# LSF0204-Breakout.net
KiCad netlist of a schematic drawn in EAGLE
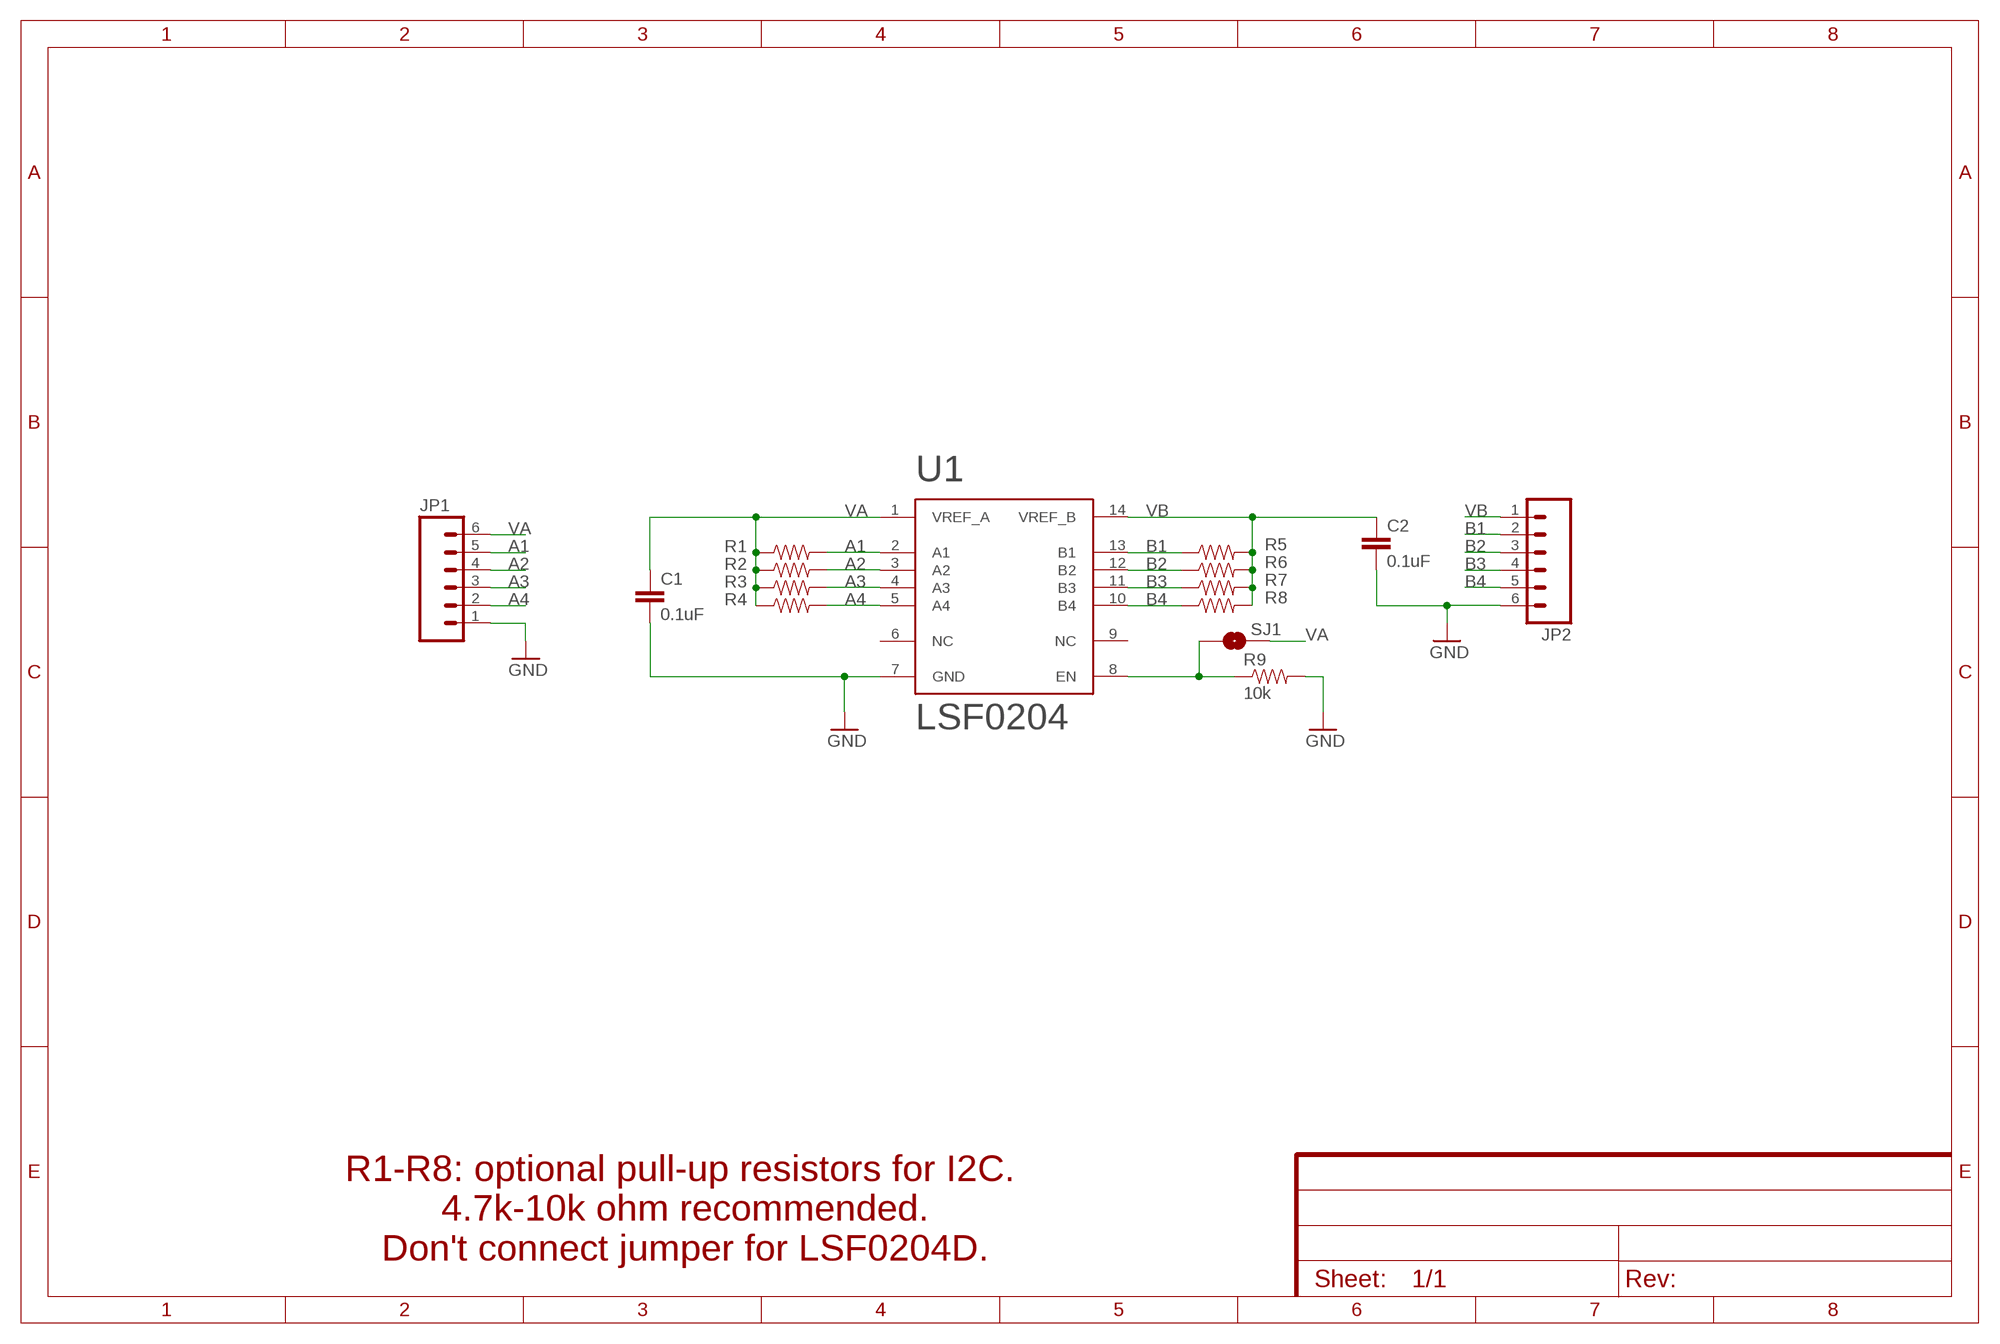
[diagram p0: schematic, sheet 1]

(export (version "E")
  (design (tool "Eeschema 10.0.6"))
  (components
    (comp (ref "C1")
      (value "0.1uF")
      (footprint "eagle-import:0805")
      (libsource (lib "eagle-import") (part "CAP0805"))
    )
    (comp (ref "C2")
      (value "0.1uF")
      (footprint "eagle-import:0805")
      (libsource (lib "eagle-import") (part "CAP0805"))
    )
    (comp (ref "JP1")
      (value "M06LOCK")
      (footprint "eagle-import:1X06_LOCK")
      (libsource (lib "eagle-import") (part "M06LOCK"))
    )
    (comp (ref "JP2")
      (value "M06LOCK")
      (footprint "eagle-import:1X06_LOCK")
      (libsource (lib "eagle-import") (part "M06LOCK"))
    )
    (comp (ref "R1")
      (value "RESISTOR0805-RES")
      (footprint "eagle-import:0805")
      (libsource (lib "eagle-import") (part "RESISTOR0805-RES"))
    )
    (comp (ref "R2")
      (value "RESISTOR0805-RES")
      (footprint "eagle-import:0805")
      (libsource (lib "eagle-import") (part "RESISTOR0805-RES"))
    )
    (comp (ref "R3")
      (value "RESISTOR0805-RES")
      (footprint "eagle-import:0805")
      (libsource (lib "eagle-import") (part "RESISTOR0805-RES"))
    )
    (comp (ref "R4")
      (value "RESISTOR0805-RES")
      (footprint "eagle-import:0805")
      (libsource (lib "eagle-import") (part "RESISTOR0805-RES"))
    )
    (comp (ref "R5")
      (value "RESISTOR0805-RES")
      (footprint "eagle-import:0805")
      (libsource (lib "eagle-import") (part "RESISTOR0805-RES"))
    )
    (comp (ref "R6")
      (value "RESISTOR0805-RES")
      (footprint "eagle-import:0805")
      (libsource (lib "eagle-import") (part "RESISTOR0805-RES"))
    )
    (comp (ref "R7")
      (value "RESISTOR0805-RES")
      (footprint "eagle-import:0805")
      (libsource (lib "eagle-import") (part "RESISTOR0805-RES"))
    )
    (comp (ref "R8")
      (value "RESISTOR0805-RES")
      (footprint "eagle-import:0805")
      (libsource (lib "eagle-import") (part "RESISTOR0805-RES"))
    )
    (comp (ref "R9")
      (value "10k")
      (footprint "eagle-import:0805")
      (libsource (lib "eagle-import") (part "RESISTOR0805-RES"))
    )
    (comp (ref "SJ1")
      (value "JUMPER-PAD-2-NO")
      (footprint "eagle-import:PAD-JUMPER-2-NO_NO_SILK")
      (libsource (lib "eagle-import") (part "JUMPER-PAD-2-NO"))
    )
    (comp (ref "U1")
      (value "LSF0204")
      (footprint "eagle-import:TSSOP_14")
      (libsource (lib "eagle-import") (part "LSF0204"))
    )
  )
  (nets
    (net (code "1") (name "/A1") (class "Default")
      (node (ref "JP1") (pin "5") (pinfunction "5_5") (pintype "passive"))
      (node (ref "R1") (pin "2") (pinfunction "2_2") (pintype "passive"))
      (node (ref "U1") (pin "2") (pinfunction "A1_2") (pintype "bidirectional"))
    )
    (net (code "2") (name "/A2") (class "Default")
      (node (ref "JP1") (pin "4") (pinfunction "4_4") (pintype "passive"))
      (node (ref "R2") (pin "2") (pinfunction "2_2") (pintype "passive"))
      (node (ref "U1") (pin "3") (pinfunction "A2_3") (pintype "bidirectional"))
    )
    (net (code "3") (name "/A3") (class "Default")
      (node (ref "JP1") (pin "3") (pinfunction "3_3") (pintype "passive"))
      (node (ref "R3") (pin "2") (pinfunction "2_2") (pintype "passive"))
      (node (ref "U1") (pin "4") (pinfunction "A3_4") (pintype "bidirectional"))
    )
    (net (code "4") (name "/A4") (class "Default")
      (node (ref "JP1") (pin "2") (pinfunction "2_2") (pintype "passive"))
      (node (ref "R4") (pin "2") (pinfunction "2_2") (pintype "passive"))
      (node (ref "U1") (pin "5") (pinfunction "A4_5") (pintype "bidirectional"))
    )
    (net (code "5") (name "/B1") (class "Default")
      (node (ref "JP2") (pin "2") (pinfunction "2_2") (pintype "passive"))
      (node (ref "R5") (pin "1") (pinfunction "1_1") (pintype "passive"))
      (node (ref "U1") (pin "13") (pinfunction "B1_13") (pintype "bidirectional"))
    )
    (net (code "6") (name "/B2") (class "Default")
      (node (ref "JP2") (pin "3") (pinfunction "3_3") (pintype "passive"))
      (node (ref "R6") (pin "1") (pinfunction "1_1") (pintype "passive"))
      (node (ref "U1") (pin "12") (pinfunction "B2_12") (pintype "bidirectional"))
    )
    (net (code "7") (name "/B3") (class "Default")
      (node (ref "JP2") (pin "4") (pinfunction "4_4") (pintype "passive"))
      (node (ref "R7") (pin "1") (pinfunction "1_1") (pintype "passive"))
      (node (ref "U1") (pin "11") (pinfunction "B3_11") (pintype "bidirectional"))
    )
    (net (code "8") (name "/B4") (class "Default")
      (node (ref "JP2") (pin "5") (pinfunction "5_5") (pintype "passive"))
      (node (ref "R8") (pin "1") (pinfunction "1_1") (pintype "passive"))
      (node (ref "U1") (pin "10") (pinfunction "B4_10") (pintype "bidirectional"))
    )
    (net (code "9") (name "/VA") (class "Default")
      (node (ref "C1") (pin "1") (pinfunction "1_1") (pintype "passive"))
      (node (ref "JP1") (pin "6") (pinfunction "6_6") (pintype "passive"))
      (node (ref "R1") (pin "1") (pinfunction "1_1") (pintype "passive"))
      (node (ref "R2") (pin "1") (pinfunction "1_1") (pintype "passive"))
      (node (ref "R3") (pin "1") (pinfunction "1_1") (pintype "passive"))
      (node (ref "R4") (pin "1") (pinfunction "1_1") (pintype "passive"))
      (node (ref "SJ1") (pin "2") (pinfunction "2_2") (pintype "passive"))
      (node (ref "U1") (pin "1") (pinfunction "VREF_A_1") (pintype "bidirectional"))
    )
    (net (code "10") (name "/VB") (class "Default")
      (node (ref "C2") (pin "1") (pinfunction "1_1") (pintype "passive"))
      (node (ref "JP2") (pin "1") (pinfunction "1_1") (pintype "passive"))
      (node (ref "R5") (pin "2") (pinfunction "2_2") (pintype "passive"))
      (node (ref "R6") (pin "2") (pinfunction "2_2") (pintype "passive"))
      (node (ref "R7") (pin "2") (pinfunction "2_2") (pintype "passive"))
      (node (ref "R8") (pin "2") (pinfunction "2_2") (pintype "passive"))
      (node (ref "U1") (pin "14") (pinfunction "VREF_B_14") (pintype "bidirectional"))
    )
    (net (code "11") (name "GND") (class "Default")
      (node (ref "C1") (pin "2") (pinfunction "2_2") (pintype "passive"))
      (node (ref "C2") (pin "2") (pinfunction "2_2") (pintype "passive"))
      (node (ref "JP1") (pin "1") (pinfunction "1_1") (pintype "passive"))
      (node (ref "JP2") (pin "6") (pinfunction "6_6") (pintype "passive"))
      (node (ref "R9") (pin "2") (pinfunction "2_2") (pintype "passive"))
      (node (ref "U1") (pin "7") (pinfunction "GND_7") (pintype "power_in"))
    )
    (net (code "12") (name "Net-(U1-EN)") (class "Default")
      (node (ref "R9") (pin "1") (pinfunction "1_1") (pintype "passive"))
      (node (ref "SJ1") (pin "1") (pinfunction "1_1") (pintype "passive"))
      (node (ref "U1") (pin "8") (pinfunction "EN_8") (pintype "bidirectional"))
    )
    (net (code "13") (name "unconnected-(U1-NC-Pad6)") (class "Default")
      (node (ref "U1") (pin "6") (pinfunction "NC_6") (pintype "no_connect"))
    )
    (net (code "14") (name "unconnected-(U1-NC-Pad9)") (class "Default")
      (node (ref "U1") (pin "9") (pinfunction "NC_9") (pintype "no_connect"))
    )
  )
)
